# hbridge_v2.net
KiCad netlist of a schematic drawn in EAGLE
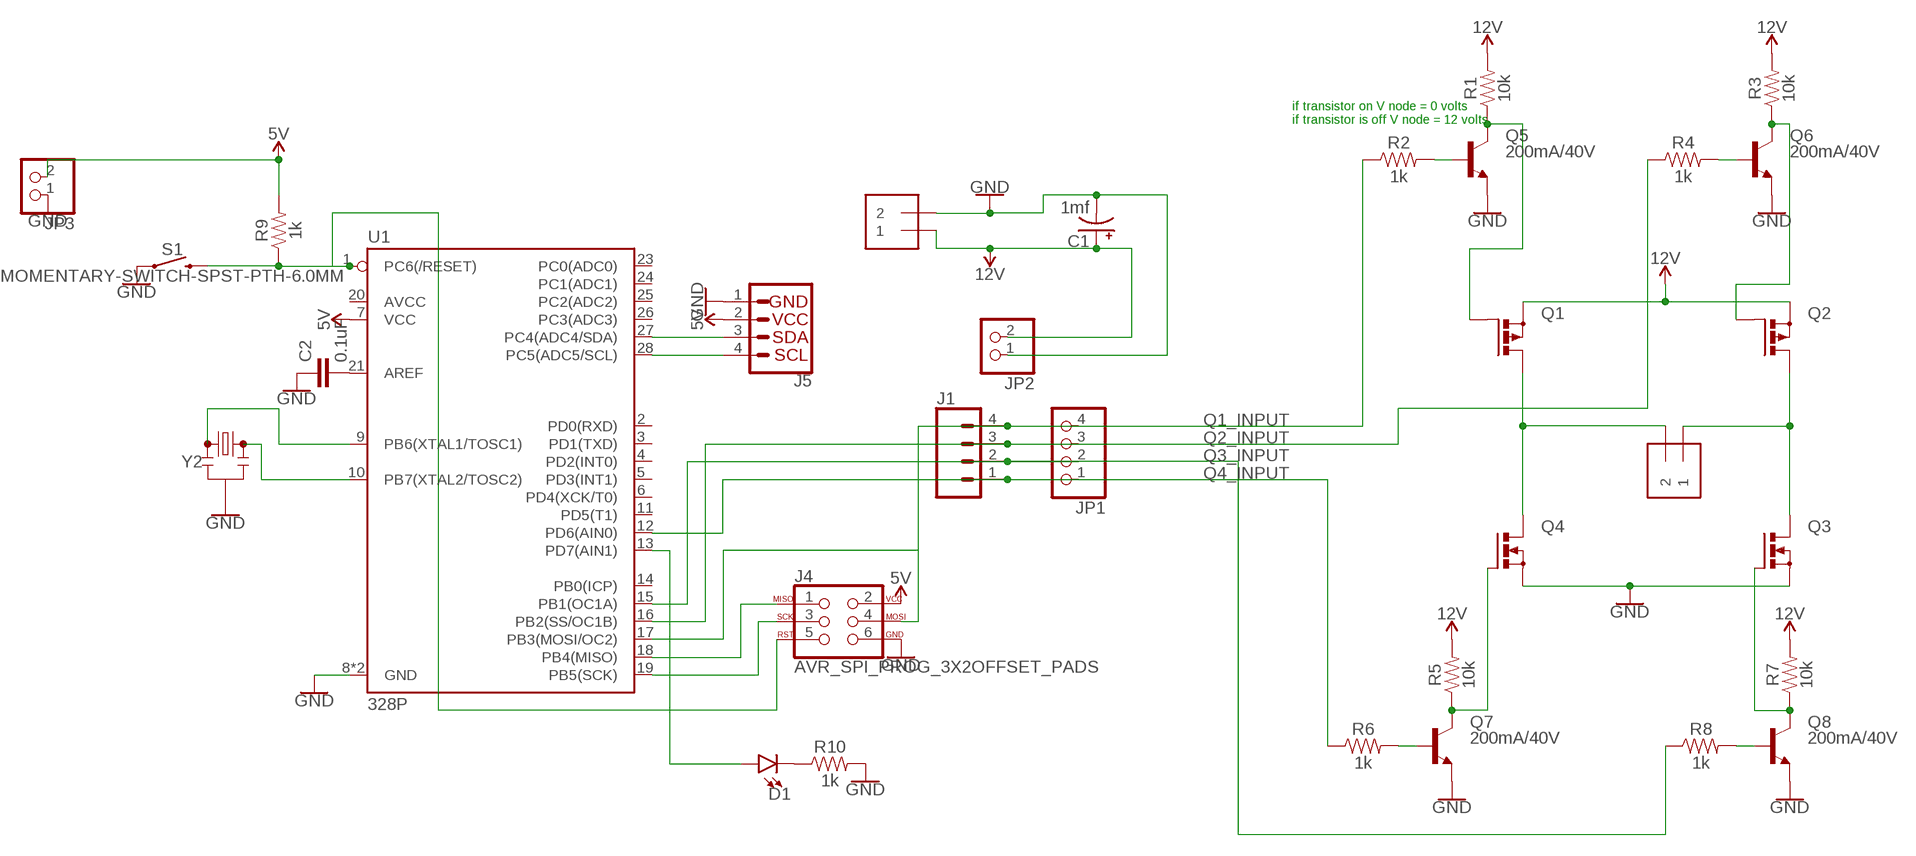
[diagram p0: schematic, sheet 1]

(export (version "E")
  (design (tool "Eeschema 10.0.6"))
  (components
    (comp (ref "C1")
      (value "1mf")
      (footprint "eagle-import:CPOL-RADIAL-5MM-10MM-KIT")
      (libsource (lib "eagle-import") (part "1000UF-RADIAL-5MM-35V-20%-KIT"))
    )
    (comp (ref "C2")
      (value "0.1uF")
      (footprint "eagle-import:CAP-PTH-SMALL-KIT")
      (libsource (lib "eagle-import") (part "0.1UF-KIT-EZ-50V-20%"))
    )
    (comp (ref "D1")
      (value "LED3MM")
      (footprint "eagle-import:LED_3MM")
      (libsource (lib "eagle-import") (part "LED3MM"))
    )
    (comp (ref "J1")
      (value "CONN_04LONGPADS")
      (footprint "eagle-import:1X04_LONGPADS")
      (libsource (lib "eagle-import") (part "CONN_04LONGPADS"))
    )
    (comp (ref "J2")
      (value "1X2-3.5MM")
      (footprint "eagle-import:1X2-3.5MM")
      (libsource (lib "eagle-import") (part "1X2-3.5MM"))
    )
    (comp (ref "J3")
      (value "1X2-3.5MM")
      (footprint "eagle-import:1X2-3.5MM")
      (libsource (lib "eagle-import") (part "1X2-3.5MM"))
    )
    (comp (ref "J4")
      (value "AVR_SPI_PROG_3X2OFFSET_PADS")
      (footprint "eagle-import:2X3_OFFSET")
      (libsource (lib "eagle-import") (part "AVR_SPI_PROG_3X2OFFSET_PADS"))
    )
    (comp (ref "J5")
      (value "I2C_STANDARD")
      (footprint "eagle-import:1X04")
      (libsource (lib "eagle-import") (part "I2C_STANDARD"))
    )
    (comp (ref "JP1")
      (value "PINHD-1X4")
      (footprint "eagle-import:1X04")
      (libsource (lib "eagle-import") (part "PINHD-1X4"))
    )
    (comp (ref "JP2")
      (value "PINHD-1X2")
      (footprint "eagle-import:1X02")
      (libsource (lib "eagle-import") (part "PINHD-1X2"))
    )
    (comp (ref "JP3")
      (value "PINHD-1X2")
      (footprint "eagle-import:1X02")
      (libsource (lib "eagle-import") (part "PINHD-1X2"))
    )
    (comp (ref "Q1")
      (value "PMOSFET_PTO220BV")
      (footprint "eagle-import:TO220BV")
      (libsource (lib "eagle-import") (part "PMOSFET_PTO220BV"))
    )
    (comp (ref "Q2")
      (value "PMOSFET_PTO220BV")
      (footprint "eagle-import:TO220BV")
      (libsource (lib "eagle-import") (part "PMOSFET_PTO220BV"))
    )
    (comp (ref "Q3")
      (value "PMOSFET_NTO220BV")
      (footprint "eagle-import:TO220BV")
      (libsource (lib "eagle-import") (part "PMOSFET_NTO220BV"))
    )
    (comp (ref "Q4")
      (value "PMOSFET_NTO220BV")
      (footprint "eagle-import:TO220BV")
      (libsource (lib "eagle-import") (part "PMOSFET_NTO220BV"))
    )
    (comp (ref "Q5")
      (value "200mA/40V")
      (footprint "eagle-import:TO-92")
      (libsource (lib "eagle-import") (part "TRANS_NPN-2N3904"))
    )
    (comp (ref "Q6")
      (value "200mA/40V")
      (footprint "eagle-import:TO-92")
      (libsource (lib "eagle-import") (part "TRANS_NPN-2N3904"))
    )
    (comp (ref "Q7")
      (value "200mA/40V")
      (footprint "eagle-import:TO-92")
      (libsource (lib "eagle-import") (part "TRANS_NPN-2N3904"))
    )
    (comp (ref "Q8")
      (value "200mA/40V")
      (footprint "eagle-import:TO-92")
      (libsource (lib "eagle-import") (part "TRANS_NPN-2N3904"))
    )
    (comp (ref "R1")
      (value "10k")
      (footprint "eagle-import:AXIAL-0.3")
      (libsource (lib "eagle-import") (part "10KOHM-HORIZ-1/4W-1%"))
    )
    (comp (ref "R2")
      (value "1k")
      (footprint "eagle-import:AXIAL-0.3")
      (libsource (lib "eagle-import") (part "1KOHM-HORIZ-1/4W-5%"))
    )
    (comp (ref "R3")
      (value "10k")
      (footprint "eagle-import:AXIAL-0.3")
      (libsource (lib "eagle-import") (part "10KOHM-HORIZ-1/4W-1%"))
    )
    (comp (ref "R4")
      (value "1k")
      (footprint "eagle-import:AXIAL-0.3")
      (libsource (lib "eagle-import") (part "1KOHM-HORIZ-1/4W-5%"))
    )
    (comp (ref "R5")
      (value "10k")
      (footprint "eagle-import:AXIAL-0.3")
      (libsource (lib "eagle-import") (part "10KOHM-HORIZ-1/4W-1%"))
    )
    (comp (ref "R6")
      (value "1k")
      (footprint "eagle-import:AXIAL-0.3")
      (libsource (lib "eagle-import") (part "1KOHM-HORIZ-1/4W-5%"))
    )
    (comp (ref "R7")
      (value "10k")
      (footprint "eagle-import:AXIAL-0.3")
      (libsource (lib "eagle-import") (part "10KOHM-HORIZ-1/4W-1%"))
    )
    (comp (ref "R8")
      (value "1k")
      (footprint "eagle-import:AXIAL-0.3")
      (libsource (lib "eagle-import") (part "1KOHM-HORIZ-1/4W-5%"))
    )
    (comp (ref "R9")
      (value "1k")
      (footprint "eagle-import:AXIAL-0.3")
      (libsource (lib "eagle-import") (part "1KOHM-HORIZ-1/4W-5%"))
    )
    (comp (ref "R10")
      (value "1k")
      (footprint "eagle-import:AXIAL-0.3")
      (libsource (lib "eagle-import") (part "1KOHM-HORIZ-1/4W-5%"))
    )
    (comp (ref "S1")
      (value "MOMENTARY-SWITCH-SPST-PTH-6.0MM")
      (footprint "eagle-import:TACTILE_SWITCH_PTH_6.0MM")
      (libsource (lib "eagle-import") (part "MOMENTARY-SWITCH-SPST-PTH-6.0MM"))
    )
    (comp (ref "U1")
      (value "328P")
      (footprint "eagle-import:DIP28")
      (libsource (lib "eagle-import") (part "ATMEGA328P_PDIP"))
    )
    (comp (ref "Y2")
      (value "RESONATORPTH-7.6X3.8")
      (footprint "eagle-import:RESONATOR-PTH-7.6X3.8")
      (libsource (lib "eagle-import") (part "RESONATORPTH-7.6X3.8"))
    )
  )
  (nets
    (net (code "1") (name "/Q1_INPUT") (class "Default")
      (node (ref "J1") (pin "4") (pinfunction "4_4") (pintype "passive"))
      (node (ref "J4") (pin "4") (pinfunction "4_4") (pintype "passive"))
      (node (ref "JP1") (pin "4") (pinfunction "4_4") (pintype "passive"))
      (node (ref "R2") (pin "P$1") (pinfunction "1_P$1") (pintype "passive"))
      (node (ref "U1") (pin "17") (pinfunction "PB3(MOSI/OC2)_17") (pintype "bidirectional"))
    )
    (net (code "2") (name "/Q2_INPUT") (class "Default")
      (node (ref "J1") (pin "3") (pinfunction "3_3") (pintype "passive"))
      (node (ref "JP1") (pin "3") (pinfunction "3_3") (pintype "passive"))
      (node (ref "R4") (pin "P$1") (pinfunction "1_P$1") (pintype "passive"))
      (node (ref "U1") (pin "16") (pinfunction "PB2(SS/OC1B)_16") (pintype "bidirectional"))
    )
    (net (code "3") (name "/Q3_INPUT") (class "Default")
      (node (ref "J1") (pin "2") (pinfunction "2_2") (pintype "passive"))
      (node (ref "JP1") (pin "2") (pinfunction "2_2") (pintype "passive"))
      (node (ref "R8") (pin "P$1") (pinfunction "1_P$1") (pintype "passive"))
      (node (ref "U1") (pin "15") (pinfunction "PB1(OC1A)_15") (pintype "bidirectional"))
    )
    (net (code "4") (name "/Q4_INPUT") (class "Default")
      (node (ref "J1") (pin "1") (pinfunction "1_1") (pintype "passive"))
      (node (ref "JP1") (pin "1") (pinfunction "1_1") (pintype "passive"))
      (node (ref "R6") (pin "P$1") (pinfunction "1_P$1") (pintype "passive"))
      (node (ref "U1") (pin "12") (pinfunction "PD6(AIN0)_12") (pintype "bidirectional"))
    )
    (net (code "5") (name "5V") (class "Default")
      (node (ref "J4") (pin "2") (pinfunction "2_2") (pintype "passive"))
      (node (ref "J5") (pin "2") (pinfunction "2_2") (pintype "power_in"))
      (node (ref "JP3") (pin "2") (pinfunction "2_2") (pintype "passive"))
      (node (ref "R9") (pin "P$2") (pinfunction "2_P$2") (pintype "passive"))
      (node (ref "U1") (pin "7") (pinfunction "VCC_7") (pintype "bidirectional"))
    )
    (net (code "6") (name "12V") (class "Default")
      (node (ref "C1") (pin "+") (pinfunction "+_+") (pintype "passive"))
      (node (ref "J3") (pin "1") (pinfunction "1_1") (pintype "passive"))
      (node (ref "JP2") (pin "2") (pinfunction "2_2") (pintype "passive"))
      (node (ref "Q1") (pin "S") (pinfunction "S_S") (pintype "passive"))
      (node (ref "Q2") (pin "S") (pinfunction "S_S") (pintype "passive"))
      (node (ref "R1") (pin "P$2") (pinfunction "2_P$2") (pintype "passive"))
      (node (ref "R3") (pin "P$2") (pinfunction "2_P$2") (pintype "passive"))
      (node (ref "R5") (pin "P$2") (pinfunction "2_P$2") (pintype "passive"))
      (node (ref "R7") (pin "P$2") (pinfunction "2_P$2") (pintype "passive"))
    )
    (net (code "7") (name "GND") (class "Default")
      (node (ref "C1") (pin "-") (pinfunction "-_-") (pintype "passive"))
      (node (ref "C2") (pin "1") (pinfunction "1_1") (pintype "passive"))
      (node (ref "J3") (pin "2") (pinfunction "2_2") (pintype "passive"))
      (node (ref "J4") (pin "6") (pinfunction "6_6") (pintype "passive"))
      (node (ref "J5") (pin "1") (pinfunction "1_1") (pintype "power_in"))
      (node (ref "JP2") (pin "1") (pinfunction "1_1") (pintype "passive"))
      (node (ref "JP3") (pin "1") (pinfunction "1_1") (pintype "passive"))
      (node (ref "Q3") (pin "S") (pinfunction "S_S") (pintype "passive"))
      (node (ref "Q4") (pin "S") (pinfunction "S_S") (pintype "passive"))
      (node (ref "Q5") (pin "1") (pinfunction "E_1") (pintype "passive"))
      (node (ref "Q6") (pin "1") (pinfunction "E_1") (pintype "passive"))
      (node (ref "Q7") (pin "1") (pinfunction "E_1") (pintype "passive"))
      (node (ref "Q8") (pin "1") (pinfunction "E_1") (pintype "passive"))
      (node (ref "R10") (pin "P$2") (pinfunction "2_P$2") (pintype "passive"))
      (node (ref "S1") (pin "1") (pinfunction "1_1") (pintype "passive"))
      (node (ref "U1") (pin "22") (pinfunction "GND_22") (pintype "bidirectional"))
      (node (ref "U1") (pin "8") (pinfunction "GND_8") (pintype "bidirectional"))
      (node (ref "Y2") (pin "2") (pinfunction "2_2") (pintype "passive"))
    )
    (net (code "8") (name "Net-(D1-C)") (class "Default")
      (node (ref "D1") (pin "K") (pinfunction "C_K") (pintype "passive"))
      (node (ref "R10") (pin "P$1") (pinfunction "1_P$1") (pintype "passive"))
    )
    (net (code "9") (name "Net-(J2-Pad1)") (class "Default")
      (node (ref "J2") (pin "1") (pinfunction "1_1") (pintype "passive"))
      (node (ref "Q2") (pin "D") (pinfunction "D_D") (pintype "passive"))
      (node (ref "Q3") (pin "D") (pinfunction "D_D") (pintype "passive"))
    )
    (net (code "10") (name "Net-(J2-Pad2)") (class "Default")
      (node (ref "J2") (pin "2") (pinfunction "2_2") (pintype "passive"))
      (node (ref "Q1") (pin "D") (pinfunction "D_D") (pintype "passive"))
      (node (ref "Q4") (pin "D") (pinfunction "D_D") (pintype "passive"))
    )
    (net (code "11") (name "Net-(Q5-B)") (class "Default")
      (node (ref "Q5") (pin "2") (pinfunction "B_2") (pintype "passive"))
      (node (ref "R2") (pin "P$2") (pinfunction "2_P$2") (pintype "passive"))
    )
    (net (code "12") (name "Net-(Q5-C)") (class "Default")
      (node (ref "Q1") (pin "G") (pinfunction "G_G") (pintype "passive"))
      (node (ref "Q5") (pin "3") (pinfunction "C_3") (pintype "passive"))
      (node (ref "R1") (pin "P$1") (pinfunction "1_P$1") (pintype "passive"))
    )
    (net (code "13") (name "Net-(Q6-B)") (class "Default")
      (node (ref "Q6") (pin "2") (pinfunction "B_2") (pintype "passive"))
      (node (ref "R4") (pin "P$2") (pinfunction "2_P$2") (pintype "passive"))
    )
    (net (code "14") (name "Net-(Q6-C)") (class "Default")
      (node (ref "Q2") (pin "G") (pinfunction "G_G") (pintype "passive"))
      (node (ref "Q6") (pin "3") (pinfunction "C_3") (pintype "passive"))
      (node (ref "R3") (pin "P$1") (pinfunction "1_P$1") (pintype "passive"))
    )
    (net (code "15") (name "Net-(Q7-B)") (class "Default")
      (node (ref "Q7") (pin "2") (pinfunction "B_2") (pintype "passive"))
      (node (ref "R6") (pin "P$2") (pinfunction "2_P$2") (pintype "passive"))
    )
    (net (code "16") (name "Net-(Q7-C)") (class "Default")
      (node (ref "Q4") (pin "G") (pinfunction "G_G") (pintype "passive"))
      (node (ref "Q7") (pin "3") (pinfunction "C_3") (pintype "passive"))
      (node (ref "R5") (pin "P$1") (pinfunction "1_P$1") (pintype "passive"))
    )
    (net (code "17") (name "Net-(Q8-B)") (class "Default")
      (node (ref "Q8") (pin "2") (pinfunction "B_2") (pintype "passive"))
      (node (ref "R8") (pin "P$2") (pinfunction "2_P$2") (pintype "passive"))
    )
    (net (code "18") (name "Net-(Q8-C)") (class "Default")
      (node (ref "Q3") (pin "G") (pinfunction "G_G") (pintype "passive"))
      (node (ref "Q8") (pin "3") (pinfunction "C_3") (pintype "passive"))
      (node (ref "R7") (pin "P$1") (pinfunction "1_P$1") (pintype "passive"))
    )
    (net (code "19") (name "Net-(R9-1)") (class "Default")
      (node (ref "J4") (pin "5") (pinfunction "5_5") (pintype "passive"))
      (node (ref "R9") (pin "P$1") (pinfunction "1_P$1") (pintype "passive"))
      (node (ref "S1") (pin "3") (pinfunction "2_3") (pintype "passive"))
      (node (ref "U1") (pin "1") (pinfunction "PC6(/RESET)_1") (pintype "bidirectional"))
    )
    (net (code "20") (name "Net-(U1-AREF)") (class "Default")
      (node (ref "C2") (pin "2") (pinfunction "2_2") (pintype "passive"))
      (node (ref "U1") (pin "21") (pinfunction "AREF_21") (pintype "bidirectional"))
    )
    (net (code "21") (name "Net-(U1-PB4(MISO))") (class "Default")
      (node (ref "J4") (pin "1") (pinfunction "1_1") (pintype "passive"))
      (node (ref "U1") (pin "18") (pinfunction "PB4(MISO)_18") (pintype "bidirectional"))
    )
    (net (code "22") (name "Net-(U1-PB5(SCK))") (class "Default")
      (node (ref "J4") (pin "3") (pinfunction "3_3") (pintype "passive"))
      (node (ref "U1") (pin "19") (pinfunction "PB5(SCK)_19") (pintype "bidirectional"))
    )
    (net (code "23") (name "Net-(U1-PB6(XTAL1{slash}TOSC1))") (class "Default")
      (node (ref "U1") (pin "9") (pinfunction "PB6(XTAL1/TOSC1)_9") (pintype "bidirectional"))
      (node (ref "Y2") (pin "1") (pinfunction "1_1") (pintype "passive"))
    )
    (net (code "24") (name "Net-(U1-PB7(XTAL2{slash}TOSC2))") (class "Default")
      (node (ref "U1") (pin "10") (pinfunction "PB7(XTAL2/TOSC2)_10") (pintype "bidirectional"))
      (node (ref "Y2") (pin "3") (pinfunction "3_3") (pintype "passive"))
    )
    (net (code "25") (name "Net-(U1-PC4(ADC4{slash}SDA))") (class "Default")
      (node (ref "J5") (pin "3") (pinfunction "3_3") (pintype "passive"))
      (node (ref "U1") (pin "27") (pinfunction "PC4(ADC4/SDA)_27") (pintype "bidirectional"))
    )
    (net (code "26") (name "Net-(U1-PC5(ADC5{slash}SCL))") (class "Default")
      (node (ref "J5") (pin "4") (pinfunction "4_4") (pintype "passive"))
      (node (ref "U1") (pin "28") (pinfunction "PC5(ADC5/SCL)_28") (pintype "bidirectional"))
    )
    (net (code "27") (name "Net-(U1-PD7(AIN1))") (class "Default")
      (node (ref "D1") (pin "A") (pinfunction "A_A") (pintype "passive"))
      (node (ref "U1") (pin "13") (pinfunction "PD7(AIN1)_13") (pintype "bidirectional"))
    )
    (net (code "28") (name "unconnected-(U1-AVCC-Pad20)") (class "Default")
      (node (ref "U1") (pin "20") (pinfunction "AVCC_20") (pintype "bidirectional"))
    )
    (net (code "29") (name "unconnected-(U1-PB0(ICP)-Pad14)") (class "Default")
      (node (ref "U1") (pin "14") (pinfunction "PB0(ICP)_14") (pintype "bidirectional"))
    )
    (net (code "30") (name "unconnected-(U1-PC0(ADC0)-Pad23)") (class "Default")
      (node (ref "U1") (pin "23") (pinfunction "PC0(ADC0)_23") (pintype "bidirectional"))
    )
    (net (code "31") (name "unconnected-(U1-PC1(ADC1)-Pad24)") (class "Default")
      (node (ref "U1") (pin "24") (pinfunction "PC1(ADC1)_24") (pintype "bidirectional"))
    )
    (net (code "32") (name "unconnected-(U1-PC2(ADC2)-Pad25)") (class "Default")
      (node (ref "U1") (pin "25") (pinfunction "PC2(ADC2)_25") (pintype "bidirectional"))
    )
    (net (code "33") (name "unconnected-(U1-PC3(ADC3)-Pad26)") (class "Default")
      (node (ref "U1") (pin "26") (pinfunction "PC3(ADC3)_26") (pintype "bidirectional"))
    )
    (net (code "34") (name "unconnected-(U1-PD0(RXD)-Pad2)") (class "Default")
      (node (ref "U1") (pin "2") (pinfunction "PD0(RXD)_2") (pintype "bidirectional"))
    )
    (net (code "35") (name "unconnected-(U1-PD1(TXD)-Pad3)") (class "Default")
      (node (ref "U1") (pin "3") (pinfunction "PD1(TXD)_3") (pintype "bidirectional"))
    )
    (net (code "36") (name "unconnected-(U1-PD2(INT0)-Pad4)") (class "Default")
      (node (ref "U1") (pin "4") (pinfunction "PD2(INT0)_4") (pintype "bidirectional"))
    )
    (net (code "37") (name "unconnected-(U1-PD3(INT1)-Pad5)") (class "Default")
      (node (ref "U1") (pin "5") (pinfunction "PD3(INT1)_5") (pintype "bidirectional"))
    )
    (net (code "38") (name "unconnected-(U1-PD4(XCK{slash}T0)-Pad6)") (class "Default")
      (node (ref "U1") (pin "6") (pinfunction "PD4(XCK/T0)_6") (pintype "bidirectional"))
    )
    (net (code "39") (name "unconnected-(U1-PD5(T1)-Pad11)") (class "Default")
      (node (ref "U1") (pin "11") (pinfunction "PD5(T1)_11") (pintype "bidirectional"))
    )
  )
)
